# Buck-converter.net
KiCad netlist of a schematic drawn in Altium Designer
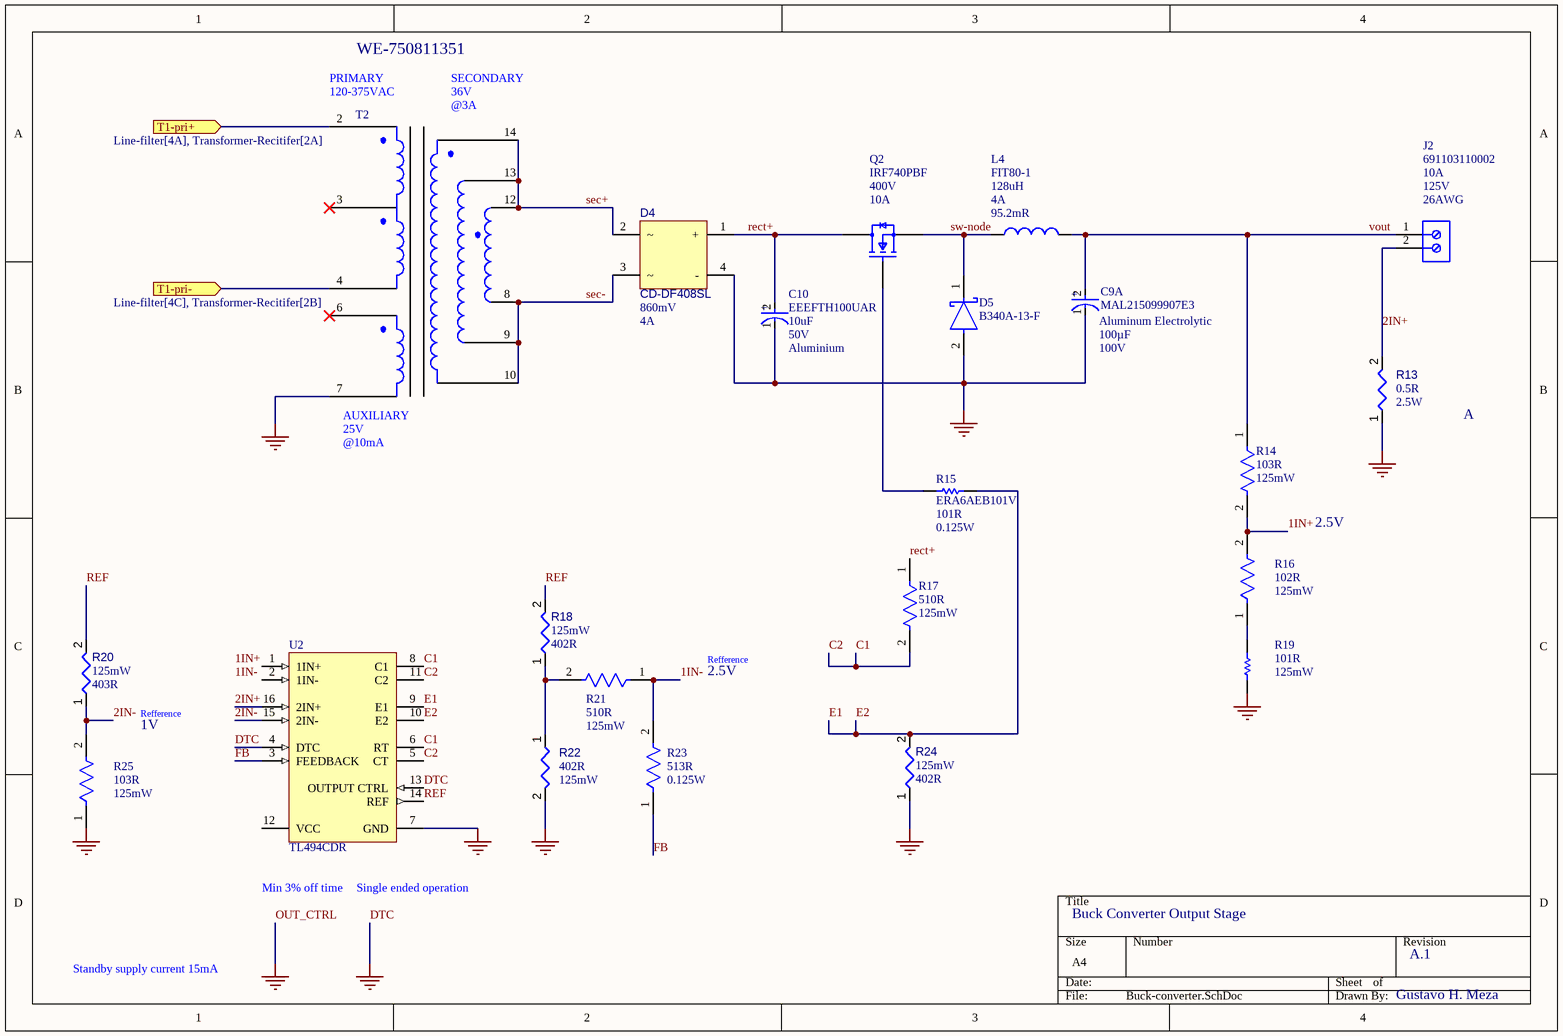
[diagram p0: Buck-converter.SchDoc]

(export (version "E")
  (design (tool "Eeschema 10.0.6"))
  (components
    (comp (ref "C9")
      (value "MAL215099907E3")
      (footprint "FP-MAL215099907E3-MFG")
      (fields
        (field (name "VOLTAGE RATING") "100V")
        (field (name "CAPACITANCE") "100µF")
        (field (name "TOLERANCE") "20%")
        (field (name "CONSTRUCTION") "Aluminum Electrolytic")
      )
      (libsource (lib "Altium Content Vault") (part "c6cab7c05467c2c24ca61f0f00c062c"))
    )
    (comp (ref "C10")
      (value "EEEFTH100UAR")
      (footprint "FP-FTB-MFG")
      (description "CAP ALUM 10UF 20% 50V SMD")
      (fields
        (field (name "CAPACITANCE") "10uF")
        (field (name "VOLTAGE RATING") "50V")
        (field (name "VOLTAGE") "50V")
        (field (name "TOLERANCE") "20%")
        (field (name "DIELECTRIC MATERIAL") "Aluminium")
      )
      (libsource (lib "Altium Content Vault") (part "a00bbbee19879c290e62620ae7e47b1"))
    )
    (comp (ref "D4")
      (value "CD-DF408SL")
      (footprint "CD-DF408SL-Footprint-1")
      (description "Bridge Rectifier Diode, 1 Phase, 4A, 800V V(RRM), Silicon")
      (fields (field (name "FORWARD VOLTAGE") "860mV") (field (name "FORWARD CURRENT") "4A"))
      (libsource (lib "Cetys University") (part "DIODE-2"))
    )
    (comp (ref "D5")
      (value "B340A-13-F")
      (footprint "FP-SMA-MFG")
      (description "DIODE SCHOTTKY 40V 3A SMA")
      (fields (field (name "VOLTAGE") "40V"))
      (libsource (lib "Altium Content Vault") (part "1d6ec82d83fb6aee721767c19dac4b9"))
    )
    (comp (ref "J2")
      (value "691103110002")
      (footprint "691103110002")
      (fields
        (field (name "CURRENT RATING") "10A")
        (field (name "VOLTAGE") "125V")
        (field (name "WIRE/CABLE GAUGE") "26AWG")
      )
      (libsource (lib "Altium Content Vault") (part "TBL - 1R - 02P - Screw"))
    )
    (comp (ref "L4")
      (value "FIT80-1")
      (footprint "FIT80-1-Footprint-1")
      (description "General Purpose Inductor, 128uH, 1 Element, 9863")
      (fields
        (field (name "DC RESISTANCE (DCR)") "95.2mR")
        (field (name "INDUCTANCE-NOM (L)") "128uH")
        (field (name "MAX CURRENT RATING") "4A")
      )
      (libsource (lib "Cetys University") (part "IND-2"))
    )
    (comp (ref "Q2")
      (value "IRF740PBF")
      (footprint "FP-X15-0364-MFG")
      (description "MOSFET N-CH 400V 10A TO-220AB")
      (fields
        (field (name "DRAIN TO SOURCE VOLTAGE") "400V")
        (field (name "CONTINUOUS DRAIN CURRENT") "10A")
        (field (name "OCTOPART") "https://octopart.com/irf740pbf-vishay-46527100")
        (field (name "MANUFACTURER") "Vishay")
      )
      (libsource (lib "Altium Content Vault") (part "b44c8776e10362b01251f5cff19d373"))
    )
    (comp (ref "R13")
      (value "0.5R")
      (footprint "RS02CR5000FB12-Footprint-1")
      (description "Fixed Resistor, Wire Wound, 2.5W, 0.5ohm, 1% +/-Tol, 90ppm/Cel, Through Hole Mount")
      (fields
        (field (name "TOLERANCE") "1%")
        (field (name "POWER") "2.5W")
        (field (name "Comment") "RS02CR5000FB12")
      )
      (libsource (lib "Cetys University") (part "RES-2"))
    )
    (comp (ref "R14")
      (value "CRCW080510K0FKEA")
      (footprint "FP-CRCW0805-e3-IPC_A")
      (description "RES Thick Film, 10kΩ, 1%, 0.125W, 100ppm/°C, 0805")
      (fields
        (field (name "RESISTANCE") "103R")
        (field (name "TOLERANCE") "1%")
        (field (name "POWER RATING") "125mW")
      )
      (libsource (lib "Altium Content Vault") (part "1029c3af85768c4190bb7ad29bc67b5"))
    )
    (comp (ref "R15")
      (value "ERA6AEB101V")
      (footprint "RESC2013X60X40ML20T25")
      (fields
        (field (name "MANUFACTURER") "Panasonic")
        (field (name "RESISTANCE") "101R")
        (field (name "POWER RATING") "0.125W")
      )
      (libsource (lib "Altium Content Vault") (part "RES"))
    )
    (comp (ref "R16")
      (value "CRCW08051K00JNEA")
      (footprint "FP-CRCW0805-e3-IPC_B")
      (description "RES Thick Film, 1kΩ, 5%, 0.125W, 200ppm/°C, 0805")
      (fields
        (field (name "POWER RATING") "125mW")
        (field (name "RESISTANCE") "102R")
        (field (name "TOLERANCE") "5%")
      )
      (libsource (lib "Altium Content Vault") (part "1029c3af85768c4190bb7ad29bc67b5"))
    )
    (comp (ref "R17")
      (value "CR0805JW511E")
      (footprint "FP-CR0805-IPC_B")
      (description "Thick Film Chip Resistors 0805 510Ω 0.125W 5% 200ppm/°C")
      (fields
        (field (name "RESISTANCE") "510R")
        (field (name "POWER RATING") "125mW")
        (field (name "TOLERANCE") "5%")
      )
      (libsource (lib "Altium Content Vault") (part "1029c3af85768c4190bb7ad29bc67b5"))
    )
    (comp (ref "R18")
      (value "402R")
      (footprint "RESC3416X05N")
      (description "RES SMD 4K OHM 1% 1/8W 0805")
      (fields
        (field (name "POWER") "125mW")
        (field (name "TOLERANCE") "1%")
        (field (name "Comment") "CRCW08054K00FKTA")
      )
      (libsource (lib "Cetys University") (part "RES-2"))
    )
    (comp (ref "R19")
      (value "ERA6AEB101V")
      (footprint "RESC2013X60X40ML20T25")
      (fields
        (field (name "MANUFACTURER") "Panasonic")
        (field (name "RESISTANCEMETER 1") "101R")
        (field (name "POWER") "125mW")
      )
      (libsource (lib "Altium Content Vault") (part "RES"))
    )
    (comp (ref "R20")
      (value "403R")
      (footprint "RESC3416X05N")
      (description "RES SMD 4K OHM 1% 1/8W 0805")
      (fields
        (field (name "POWER") "125mW")
        (field (name "TOLERANCE") "1%")
        (field (name "Comment") "CRCW08054K00FKTA")
      )
      (libsource (lib "Cetys University") (part "RES-2"))
    )
    (comp (ref "R21")
      (value "CR0805JW511E")
      (footprint "FP-CR0805-IPC_B")
      (description "Thick Film Chip Resistors 0805 510Ω 0.125W 5% 200ppm/°C")
      (fields
        (field (name "RESISTANCE") "510R")
        (field (name "POWER RATING") "125mW")
        (field (name "TOLERANCE") "5%")
      )
      (libsource (lib "Altium Content Vault") (part "1029c3af85768c4190bb7ad29bc67b5"))
    )
    (comp (ref "R22")
      (value "402R")
      (footprint "RESC3416X05N")
      (description "RES SMD 4K OHM 1% 1/8W 0805")
      (fields
        (field (name "POWER") "125mW")
        (field (name "TOLERANCE") "1%")
        (field (name "Comment") "CRCW08054K00FKTA")
      )
      (libsource (lib "Cetys University") (part "RES-2"))
    )
    (comp (ref "R23")
      (value "513R")
      (footprint "FP-RT0805-MFG")
      (description "RES SMD 51K OHM 0.1% 1/8W 0805")
      (fields
        (field (name "MANUFACTURER") "Yageo")
        (field (name "TOLERANCE") "0.0025")
        (field (name "POWER RATING") "0.125W")
      )
      (libsource (lib "Altium Content Vault") (part "1029c3af85768c4190bb7ad29bc67b5"))
    )
    (comp (ref "R24")
      (value "402R")
      (footprint "RESC3416X05N")
      (description "RES SMD 4K OHM 1% 1/8W 0805")
      (fields
        (field (name "POWER") "125mW")
        (field (name "TOLERANCE") "1%")
        (field (name "Comment") "CRCW08054K00FKTA")
      )
      (libsource (lib "Cetys University") (part "RES-2"))
    )
    (comp (ref "R25")
      (value "ERA6AEB102V")
      (footprint "FP-ERA6A-IPC_C")
      (description "RES 1K OHM 0.1% 1/8W 0805")
      (fields
        (field (name "RESISTANCE") "103R")
        (field (name "MAX POWER DISSIPATION") "125mW")
        (field (name "TOLERANCE") "0.1%")
      )
      (libsource (lib "Altium Content Vault") (part "1029c3af85768c4190bb7ad29bc67b5"))
    )
    (comp (ref "T2")
      (value "WE-750811351")
      (footprint "WE-750811248-Footprint-1")
      (description "Power Transformers MID-L3798/99 Offline Isol 3.6uH +-10%")
      (fields (field (name "POWER") "48W"))
      (libsource (lib "Cetys University") (part "TFORM-4"))
    )
    (comp (ref "U2")
      (value "TL494CDR")
      (footprint "D0016A_N")
      (fields (field (name "MANUFACTURER") "Texas Instruments"))
      (libsource (lib "Altium Content Vault") (part "TI-494D16"))
    )
  )
  (nets
    (net (code "1") (name "/1IN+") (class "Default")
      (node (ref "R14") (pin "2") (pinfunction "2_2") (pintype "passive"))
      (node (ref "R16") (pin "2") (pinfunction "2_2") (pintype "passive"))
    )
    (net (code "2") (name "/1IN-") (class "Default")
      (node (ref "R21") (pin "1") (pinfunction "1_1") (pintype "passive"))
      (node (ref "R23") (pin "2") (pinfunction "2_2") (pintype "passive"))
    )
    (net (code "3") (name "/2IN+") (class "Default")
      (node (ref "J2") (pin "2") (pinfunction "2_2") (pintype "passive"))
      (node (ref "R13") (pin "2") (pinfunction "2_2") (pintype "passive"))
      (node (ref "U2") (pin "16") (pinfunction "2IN+_16") (pintype "input"))
    )
    (net (code "4") (name "/2IN-") (class "Default")
      (node (ref "R20") (pin "1") (pinfunction "1_1") (pintype "passive"))
      (node (ref "R25") (pin "2") (pinfunction "2_2") (pintype "passive"))
      (node (ref "U2") (pin "15") (pinfunction "2IN-_15") (pintype "input"))
    )
    (net (code "5") (name "/C1") (class "Default")
      (node (ref "R17") (pin "2") (pinfunction "2_2") (pintype "passive"))
      (node (ref "U2") (pin "11") (pinfunction "C2_11") (pintype "passive"))
      (node (ref "U2") (pin "5") (pinfunction "CT_5") (pintype "passive"))
      (node (ref "U2") (pin "6") (pinfunction "RT_6") (pintype "passive"))
      (node (ref "U2") (pin "8") (pinfunction "C1_8") (pintype "passive"))
    )
    (net (code "6") (name "/E1") (class "Default")
      (node (ref "R15") (pin "1") (pinfunction "1_1") (pintype "passive"))
      (node (ref "R24") (pin "2") (pinfunction "2_2") (pintype "passive"))
      (node (ref "U2") (pin "10") (pinfunction "E2_10") (pintype "passive"))
      (node (ref "U2") (pin "9") (pinfunction "E1_9") (pintype "passive"))
    )
    (net (code "7") (name "/FB") (class "Default")
      (node (ref "R23") (pin "1") (pinfunction "1_1") (pintype "passive"))
      (node (ref "U2") (pin "3") (pinfunction "FEEDBACK_3") (pintype "input"))
    )
    (net (code "8") (name "/REF") (class "Default")
      (node (ref "R18") (pin "2") (pinfunction "2_2") (pintype "passive"))
      (node (ref "R20") (pin "2") (pinfunction "2_2") (pintype "passive"))
      (node (ref "U2") (pin "14") (pinfunction "REF_14") (pintype "output"))
    )
    (net (code "9") (name "/T1-pri+") (class "Default")
      (node (ref "T2") (pin "2") (pinfunction "2_2") (pintype "passive"))
    )
    (net (code "10") (name "/T1-pri-") (class "Default")
      (node (ref "T2") (pin "4") (pinfunction "4_4") (pintype "passive"))
    )
    (net (code "11") (name "/rect+") (class "Default")
      (node (ref "C10") (pin "2") (pinfunction "A_2") (pintype "passive"))
      (node (ref "D4") (pin "1") (pinfunction "+_1") (pintype "passive"))
      (node (ref "Q2") (pin "2") (pinfunction "D_2") (pintype "passive"))
      (node (ref "R17") (pin "1") (pinfunction "1_1") (pintype "passive"))
    )
    (net (code "12") (name "/sec+") (class "Default")
      (node (ref "D4") (pin "2") (pinfunction "~_2") (pintype "passive"))
      (node (ref "T2") (pin "12") (pinfunction "12_12") (pintype "passive"))
      (node (ref "T2") (pin "13") (pinfunction "13_13") (pintype "passive"))
      (node (ref "T2") (pin "14") (pinfunction "14_14") (pintype "passive"))
    )
    (net (code "13") (name "/sec-") (class "Default")
      (node (ref "D4") (pin "3") (pinfunction "~_3") (pintype "passive"))
      (node (ref "T2") (pin "10") (pinfunction "10_10") (pintype "passive"))
      (node (ref "T2") (pin "8") (pinfunction "8_8") (pintype "passive"))
      (node (ref "T2") (pin "9") (pinfunction "9_9") (pintype "passive"))
    )
    (net (code "14") (name "/sw-node") (class "Default")
      (node (ref "D5") (pin "1") (pinfunction "C_1") (pintype "passive"))
      (node (ref "L4") (pin "1") (pinfunction "1_1") (pintype "passive"))
      (node (ref "Q2") (pin "3") (pinfunction "S_3") (pintype "passive"))
    )
    (net (code "15") (name "/vout") (class "Default")
      (node (ref "C9") (pin "2") (pinfunction "A_2") (pintype "passive"))
      (node (ref "J2") (pin "1") (pinfunction "1_1") (pintype "passive"))
      (node (ref "L4") (pin "2") (pinfunction "2_2") (pintype "passive"))
      (node (ref "R14") (pin "1") (pinfunction "1_1") (pintype "passive"))
    )
    (net (code "16") (name "GND") (class "Default")
      (node (ref "C10") (pin "1") (pinfunction "C_1") (pintype "passive"))
      (node (ref "C9") (pin "1") (pinfunction "C_1") (pintype "passive"))
      (node (ref "D4") (pin "4") (pinfunction "-_4") (pintype "passive"))
      (node (ref "D5") (pin "2") (pinfunction "A_2") (pintype "passive"))
      (node (ref "R13") (pin "1") (pinfunction "1_1") (pintype "passive"))
      (node (ref "R19") (pin "1") (pinfunction "1_1") (pintype "passive"))
      (node (ref "R22") (pin "2") (pinfunction "2_2") (pintype "passive"))
      (node (ref "R24") (pin "1") (pinfunction "1_1") (pintype "passive"))
      (node (ref "R25") (pin "1") (pinfunction "1_1") (pintype "passive"))
      (node (ref "T2") (pin "7") (pinfunction "7_7") (pintype "passive"))
      (node (ref "U2") (pin "13") (pinfunction "OUTPUT_CTRL_13") (pintype "input"))
      (node (ref "U2") (pin "4") (pinfunction "DTC_4") (pintype "input"))
      (node (ref "U2") (pin "7") (pinfunction "GND_7") (pintype "power_in"))
    )
    (net (code "17") (name "Net-(Q2-G)") (class "Default")
      (node (ref "Q2") (pin "1") (pinfunction "G_1") (pintype "passive"))
      (node (ref "R15") (pin "2") (pinfunction "2_2") (pintype "passive"))
    )
    (net (code "18") (name "Net-(R16-Pad1)") (class "Default")
      (node (ref "R16") (pin "1") (pinfunction "1_1") (pintype "passive"))
      (node (ref "R19") (pin "2") (pinfunction "2_2") (pintype "passive"))
    )
    (net (code "19") (name "Net-(R18-Pad1)") (class "Default")
      (node (ref "R18") (pin "1") (pinfunction "1_1") (pintype "passive"))
      (node (ref "R21") (pin "2") (pinfunction "2_2") (pintype "passive"))
      (node (ref "R22") (pin "1") (pinfunction "1_1") (pintype "passive"))
    )
    (net (code "20") (name "unconnected-(T2-Pad1)") (class "Default")
      (node (ref "T2") (pin "1") (pinfunction "1_1") (pintype "passive"))
    )
    (net (code "21") (name "unconnected-(T2-Pad1)_1") (class "Default")
      (node (ref "T2") (pin "1") (pinfunction "1_1") (pintype "passive"))
    )
    (net (code "22") (name "unconnected-(T2-Pad1)_2") (class "Default")
      (node (ref "T2") (pin "1") (pinfunction "1_1") (pintype "passive"))
    )
    (net (code "23") (name "unconnected-(T2-Pad2)") (class "Default")
      (node (ref "T2") (pin "2") (pinfunction "2_2") (pintype "passive"))
    )
    (net (code "24") (name "unconnected-(T2-Pad2)_1") (class "Default")
      (node (ref "T2") (pin "2") (pinfunction "2_2") (pintype "passive"))
    )
    (net (code "25") (name "unconnected-(T2-Pad2)_2") (class "Default")
      (node (ref "T2") (pin "2") (pinfunction "2_2") (pintype "passive"))
    )
    (net (code "26") (name "unconnected-(T2-Pad2)_3") (class "Default")
      (node (ref "T2") (pin "2") (pinfunction "2_2") (pintype "passive"))
    )
    (net (code "27") (name "unconnected-(T2-Pad3)") (class "Default")
      (node (ref "T2") (pin "3") (pinfunction "3_3") (pintype "passive+no_connect"))
    )
    (net (code "28") (name "unconnected-(T2-Pad3)") (class "Default")
      (node (ref "T2") (pin "3") (pinfunction "3_3") (pintype "passive"))
    )
    (net (code "29") (name "unconnected-(T2-Pad4)") (class "Default")
      (node (ref "T2") (pin "4") (pinfunction "4_4") (pintype "passive"))
    )
    (net (code "30") (name "unconnected-(T2-Pad6)") (class "Default")
      (node (ref "T2") (pin "6") (pinfunction "6_6") (pintype "passive+no_connect"))
    )
    (net (code "31") (name "unconnected-(U2-1IN+-Pad1)") (class "Default")
      (node (ref "U2") (pin "1") (pinfunction "1IN+_1") (pintype "input"))
    )
    (net (code "32") (name "unconnected-(U2-1IN--Pad2)") (class "Default")
      (node (ref "U2") (pin "2") (pinfunction "1IN-_2") (pintype "input"))
    )
    (net (code "33") (name "unconnected-(U2-VCC-Pad12)") (class "Default")
      (node (ref "U2") (pin "12") (pinfunction "VCC_12") (pintype "power_in"))
    )
  )
)
